# SCH_New-Project_2026-06-15.net
KiCad netlist of a schematic drawn in EasyEDA
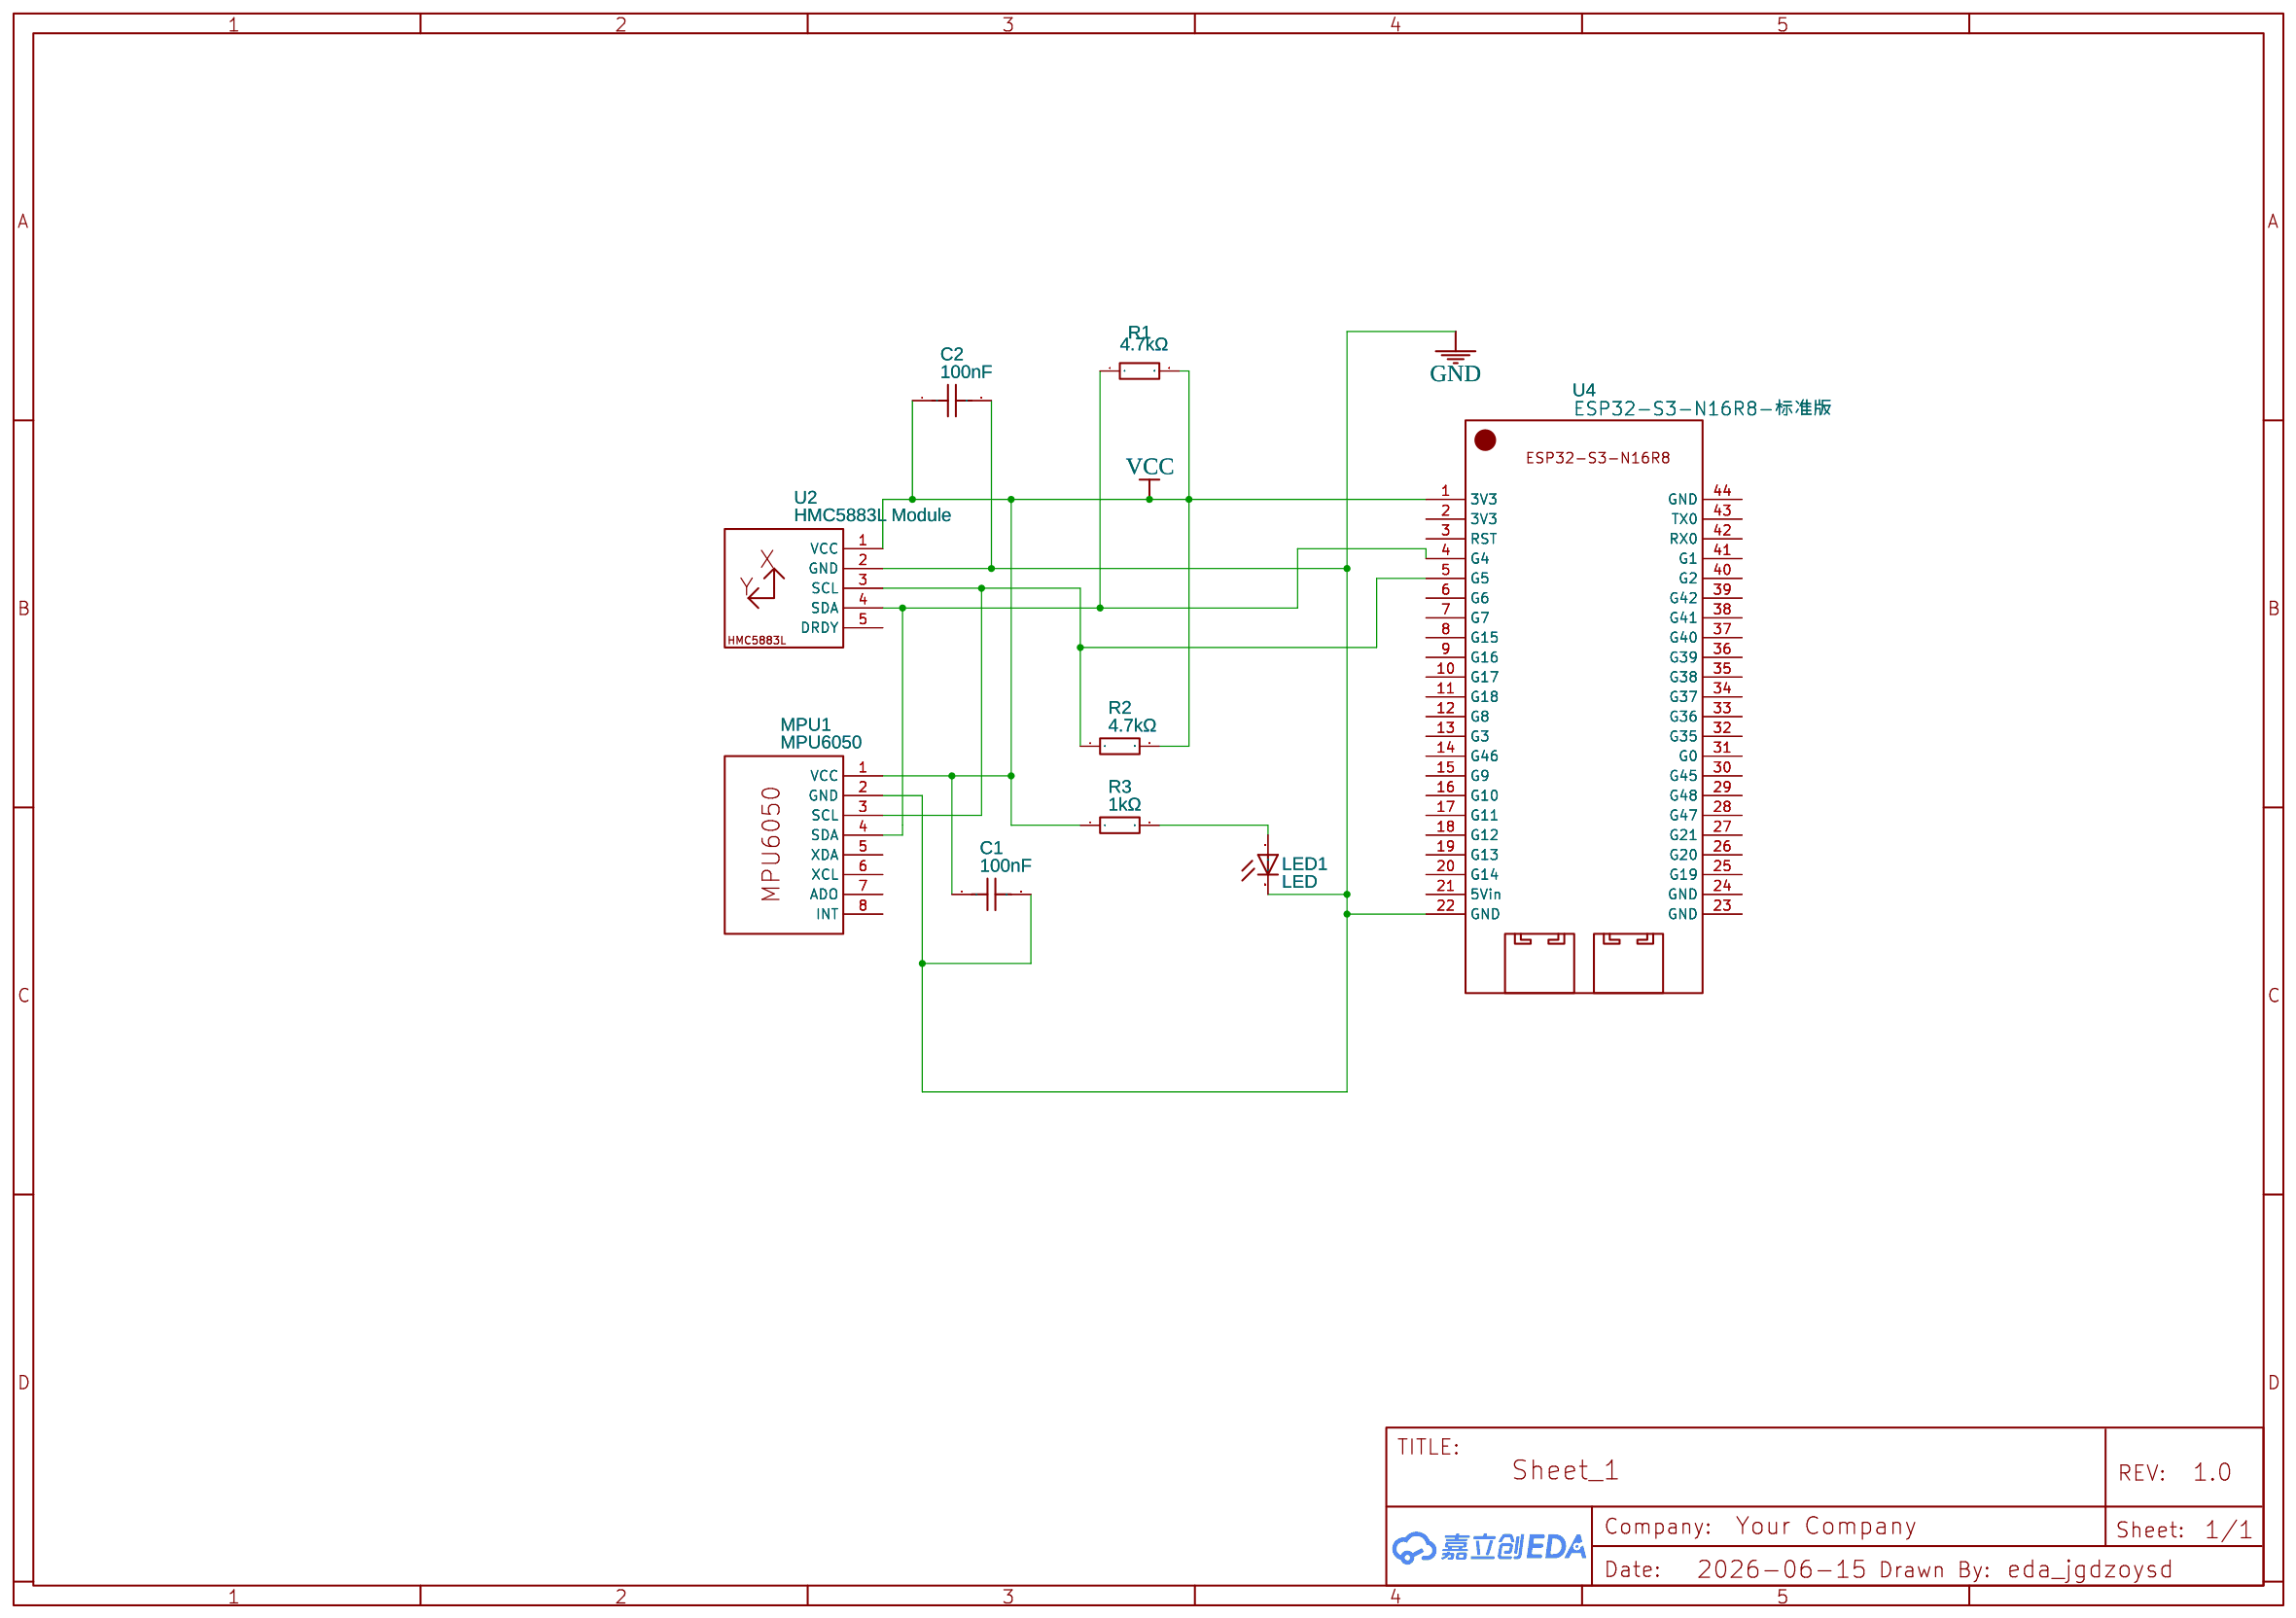
[diagram p0: schematic sheet]

(export (version "E")
  (design (tool "Eeschema 10.0.6"))
  (components
    (comp (ref "C1")
      (value "100nF")
      (fields (field (name "Manufacturer Part") "PMPR104J400D02") (field (name "Manufacturer") "TENTA(天泰)"))
      (libsource (lib "") (part "PMPR104J400D02"))
    )
    (comp (ref "C2")
      (value "100nF")
      (fields (field (name "Manufacturer Part") "PMPR104J400D02") (field (name "Manufacturer") "TENTA(天泰)"))
      (libsource (lib "") (part "PMPR104J400D02"))
    )
    (comp (ref "LED1") (value "LED") (libsource (lib "") (part "LED")))
    (comp (ref "MPU1") (value "MPU6050") (libsource (lib "") (part "MPU6050 有孔(锁定丝印)")))
    (comp (ref "R1")
      (value "4.7kΩ")
      (fields
        (field (name "Manufacturer Part") "LE03WAF470KT5E")
        (field (name "Manufacturer") "UNI-ROYAL(厚声)")
      )
      (libsource (lib "") (part "LE03WAF470KT5E"))
    )
    (comp (ref "R2")
      (value "4.7kΩ")
      (fields
        (field (name "Manufacturer Part") "LE03WAF470KT5E")
        (field (name "Manufacturer") "UNI-ROYAL(厚声)")
      )
      (libsource (lib "") (part "LE03WAF470KT5E"))
    )
    (comp (ref "R3")
      (value "1kΩ")
      (fields (field (name "Manufacturer Part") "PCF2CT631R102K") (field (name "Manufacturer") "KOA"))
      (libsource (lib "") (part "PCF2CT631R102K"))
    )
    (comp (ref "U2") (value "HMC5883L Module") (libsource (lib "") (part "HMC5883L Module")))
    (comp (ref "U4") (value "ESP32-S3-N16R8-标准版") (libsource (lib "") (part "ESP32-S3-N16R8-标准版")))
  )
  (nets
    (net (code "1") (name "GND") (class "Default")
      (node (ref "C1") (pin "2") (pinfunction "2_2") (pintype "unspecified"))
      (node (ref "C2") (pin "2") (pinfunction "2_2") (pintype "unspecified"))
      (node (ref "LED1") (pin "C@1") (pinfunction "C_C@1") (pintype "unspecified"))
      (node (ref "MPU1") (pin "2") (pinfunction "GND_2") (pintype "unspecified"))
      (node (ref "U2") (pin "2") (pinfunction "GND_2") (pintype "unspecified"))
      (node (ref "U4") (pin "22") (pinfunction "GND_22") (pintype "unspecified"))
    )
    (net (code "2") (name "Net-(LED1-A)") (class "Default")
      (node (ref "LED1") (pin "A@1") (pinfunction "A_A@1") (pintype "unspecified"))
      (node (ref "R3") (pin "2") (pinfunction "2_2") (pintype "unspecified"))
    )
    (net (code "3") (name "Net-(MPU1-SCL)") (class "Default")
      (node (ref "MPU1") (pin "3") (pinfunction "SCL_3") (pintype "unspecified"))
      (node (ref "R2") (pin "1") (pinfunction "1_1") (pintype "input"))
      (node (ref "U2") (pin "3") (pinfunction "SCL_3") (pintype "unspecified"))
      (node (ref "U4") (pin "5") (pinfunction "G5_5") (pintype "unspecified"))
    )
    (net (code "4") (name "Net-(MPU1-SDA)") (class "Default")
      (node (ref "MPU1") (pin "4") (pinfunction "SDA_4") (pintype "unspecified"))
      (node (ref "R1") (pin "1") (pinfunction "1_1") (pintype "input"))
      (node (ref "U2") (pin "4") (pinfunction "SDA_4") (pintype "unspecified"))
      (node (ref "U4") (pin "4") (pinfunction "G4_4") (pintype "unspecified"))
    )
    (net (code "5") (name "VCC") (class "Default")
      (node (ref "C1") (pin "1") (pinfunction "1_1") (pintype "unspecified"))
      (node (ref "C2") (pin "1") (pinfunction "1_1") (pintype "unspecified"))
      (node (ref "MPU1") (pin "1") (pinfunction "VCC_1") (pintype "unspecified"))
      (node (ref "R1") (pin "2") (pinfunction "2_2") (pintype "input"))
      (node (ref "R2") (pin "2") (pinfunction "2_2") (pintype "input"))
      (node (ref "R3") (pin "1") (pinfunction "1_1") (pintype "unspecified"))
      (node (ref "U2") (pin "1") (pinfunction "VCC_1") (pintype "unspecified"))
      (node (ref "U4") (pin "1") (pinfunction "3V3_1") (pintype "unspecified"))
    )
    (net (code "6") (name "unconnected-(MPU1-ADO-Pad7)") (class "Default")
      (node (ref "MPU1") (pin "7") (pinfunction "ADO_7") (pintype "unspecified"))
    )
    (net (code "7") (name "unconnected-(MPU1-INT-Pad8)") (class "Default")
      (node (ref "MPU1") (pin "8") (pinfunction "INT_8") (pintype "unspecified"))
    )
    (net (code "8") (name "unconnected-(MPU1-XCL-Pad6)") (class "Default")
      (node (ref "MPU1") (pin "6") (pinfunction "XCL_6") (pintype "unspecified"))
    )
    (net (code "9") (name "unconnected-(MPU1-XDA-Pad5)") (class "Default")
      (node (ref "MPU1") (pin "5") (pinfunction "XDA_5") (pintype "unspecified"))
    )
    (net (code "10") (name "unconnected-(U2-DRDY-Pad5)") (class "Default")
      (node (ref "U2") (pin "5") (pinfunction "DRDY_5") (pintype "unspecified"))
    )
    (net (code "11") (name "unconnected-(U4-3V3-Pad2)") (class "Default")
      (node (ref "U4") (pin "2") (pinfunction "3V3_2") (pintype "unspecified"))
    )
    (net (code "12") (name "unconnected-(U4-5Vin-Pad21)") (class "Default")
      (node (ref "U4") (pin "21") (pinfunction "5Vin_21") (pintype "unspecified"))
    )
    (net (code "13") (name "unconnected-(U4-G0-Pad31)") (class "Default")
      (node (ref "U4") (pin "31") (pinfunction "G0_31") (pintype "unspecified"))
    )
    (net (code "14") (name "unconnected-(U4-G1-Pad41)") (class "Default")
      (node (ref "U4") (pin "41") (pinfunction "G1_41") (pintype "unspecified"))
    )
    (net (code "15") (name "unconnected-(U4-G2-Pad40)") (class "Default")
      (node (ref "U4") (pin "40") (pinfunction "G2_40") (pintype "unspecified"))
    )
    (net (code "16") (name "unconnected-(U4-G3-Pad13)") (class "Default")
      (node (ref "U4") (pin "13") (pinfunction "G3_13") (pintype "unspecified"))
    )
    (net (code "17") (name "unconnected-(U4-G6-Pad6)") (class "Default")
      (node (ref "U4") (pin "6") (pinfunction "G6_6") (pintype "unspecified"))
    )
    (net (code "18") (name "unconnected-(U4-G7-Pad7)") (class "Default")
      (node (ref "U4") (pin "7") (pinfunction "G7_7") (pintype "unspecified"))
    )
    (net (code "19") (name "unconnected-(U4-G8-Pad12)") (class "Default")
      (node (ref "U4") (pin "12") (pinfunction "G8_12") (pintype "unspecified"))
    )
    (net (code "20") (name "unconnected-(U4-G9-Pad15)") (class "Default")
      (node (ref "U4") (pin "15") (pinfunction "G9_15") (pintype "unspecified"))
    )
    (net (code "21") (name "unconnected-(U4-G10-Pad16)") (class "Default")
      (node (ref "U4") (pin "16") (pinfunction "G10_16") (pintype "unspecified"))
    )
    (net (code "22") (name "unconnected-(U4-G11-Pad17)") (class "Default")
      (node (ref "U4") (pin "17") (pinfunction "G11_17") (pintype "unspecified"))
    )
    (net (code "23") (name "unconnected-(U4-G12-Pad18)") (class "Default")
      (node (ref "U4") (pin "18") (pinfunction "G12_18") (pintype "unspecified"))
    )
    (net (code "24") (name "unconnected-(U4-G13-Pad19)") (class "Default")
      (node (ref "U4") (pin "19") (pinfunction "G13_19") (pintype "unspecified"))
    )
    (net (code "25") (name "unconnected-(U4-G14-Pad20)") (class "Default")
      (node (ref "U4") (pin "20") (pinfunction "G14_20") (pintype "unspecified"))
    )
    (net (code "26") (name "unconnected-(U4-G15-Pad8)") (class "Default")
      (node (ref "U4") (pin "8") (pinfunction "G15_8") (pintype "unspecified"))
    )
    (net (code "27") (name "unconnected-(U4-G16-Pad9)") (class "Default")
      (node (ref "U4") (pin "9") (pinfunction "G16_9") (pintype "unspecified"))
    )
    (net (code "28") (name "unconnected-(U4-G17-Pad10)") (class "Default")
      (node (ref "U4") (pin "10") (pinfunction "G17_10") (pintype "unspecified"))
    )
    (net (code "29") (name "unconnected-(U4-G18-Pad11)") (class "Default")
      (node (ref "U4") (pin "11") (pinfunction "G18_11") (pintype "unspecified"))
    )
    (net (code "30") (name "unconnected-(U4-G19-Pad25)") (class "Default")
      (node (ref "U4") (pin "25") (pinfunction "G19_25") (pintype "unspecified"))
    )
    (net (code "31") (name "unconnected-(U4-G20-Pad26)") (class "Default")
      (node (ref "U4") (pin "26") (pinfunction "G20_26") (pintype "unspecified"))
    )
    (net (code "32") (name "unconnected-(U4-G21-Pad27)") (class "Default")
      (node (ref "U4") (pin "27") (pinfunction "G21_27") (pintype "unspecified"))
    )
    (net (code "33") (name "unconnected-(U4-G35-Pad32)") (class "Default")
      (node (ref "U4") (pin "32") (pinfunction "G35_32") (pintype "unspecified"))
    )
    (net (code "34") (name "unconnected-(U4-G36-Pad33)") (class "Default")
      (node (ref "U4") (pin "33") (pinfunction "G36_33") (pintype "unspecified"))
    )
    (net (code "35") (name "unconnected-(U4-G37-Pad34)") (class "Default")
      (node (ref "U4") (pin "34") (pinfunction "G37_34") (pintype "unspecified"))
    )
    (net (code "36") (name "unconnected-(U4-G38-Pad35)") (class "Default")
      (node (ref "U4") (pin "35") (pinfunction "G38_35") (pintype "unspecified"))
    )
    (net (code "37") (name "unconnected-(U4-G39-Pad36)") (class "Default")
      (node (ref "U4") (pin "36") (pinfunction "G39_36") (pintype "unspecified"))
    )
    (net (code "38") (name "unconnected-(U4-G40-Pad37)") (class "Default")
      (node (ref "U4") (pin "37") (pinfunction "G40_37") (pintype "unspecified"))
    )
    (net (code "39") (name "unconnected-(U4-G41-Pad38)") (class "Default")
      (node (ref "U4") (pin "38") (pinfunction "G41_38") (pintype "unspecified"))
    )
    (net (code "40") (name "unconnected-(U4-G42-Pad39)") (class "Default")
      (node (ref "U4") (pin "39") (pinfunction "G42_39") (pintype "unspecified"))
    )
    (net (code "41") (name "unconnected-(U4-G45-Pad30)") (class "Default")
      (node (ref "U4") (pin "30") (pinfunction "G45_30") (pintype "unspecified"))
    )
    (net (code "42") (name "unconnected-(U4-G46-Pad14)") (class "Default")
      (node (ref "U4") (pin "14") (pinfunction "G46_14") (pintype "unspecified"))
    )
    (net (code "43") (name "unconnected-(U4-G47-Pad28)") (class "Default")
      (node (ref "U4") (pin "28") (pinfunction "G47_28") (pintype "unspecified"))
    )
    (net (code "44") (name "unconnected-(U4-G48-Pad29)") (class "Default")
      (node (ref "U4") (pin "29") (pinfunction "G48_29") (pintype "unspecified"))
    )
    (net (code "45") (name "unconnected-(U4-GND-Pad23)") (class "Default")
      (node (ref "U4") (pin "23") (pinfunction "GND_23") (pintype "unspecified"))
    )
    (net (code "46") (name "unconnected-(U4-GND-Pad24)") (class "Default")
      (node (ref "U4") (pin "24") (pinfunction "GND_24") (pintype "unspecified"))
    )
    (net (code "47") (name "unconnected-(U4-GND-Pad44)") (class "Default")
      (node (ref "U4") (pin "44") (pinfunction "GND_44") (pintype "unspecified"))
    )
    (net (code "48") (name "unconnected-(U4-RST-Pad3)") (class "Default")
      (node (ref "U4") (pin "3") (pinfunction "RST_3") (pintype "unspecified"))
    )
    (net (code "49") (name "unconnected-(U4-RX0-Pad42)") (class "Default")
      (node (ref "U4") (pin "42") (pinfunction "RX0_42") (pintype "unspecified"))
    )
    (net (code "50") (name "unconnected-(U4-TX0-Pad43)") (class "Default")
      (node (ref "U4") (pin "43") (pinfunction "TX0_43") (pintype "unspecified"))
    )
  )
)
